# power_supply.net
KiCad netlist of a schematic drawn in Altium Designer
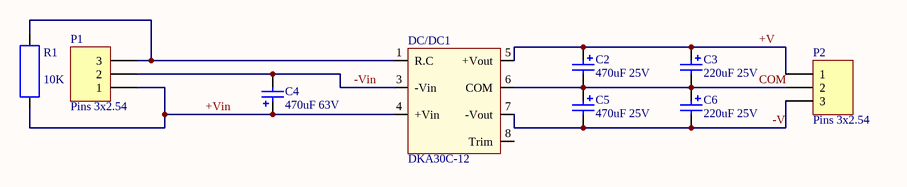
[diagram p0: power_supply.SchDoc]

(export (version "E")
  (design (tool "Eeschema 10.0.6"))
  (components
    (comp (ref "C2")
      (value "470uF 25V")
      (footprint "Cond 10mm 25V")
      (libsource (lib "A_H_sch_lib") (part "Cond_polar"))
    )
    (comp (ref "C3")
      (value "220uF 25V")
      (footprint "A_H_pcb_lib:Cond 8mm 25V")
      (libsource (lib "A_H_sch_lib") (part "Cond_polar"))
    )
    (comp (ref "C4")
      (value "470uF 63V")
      (footprint "A_H_pcb_lib:Cond 12mm 63V")
      (libsource (lib "A_H_sch_lib") (part "Cond_polar"))
    )
    (comp (ref "C5")
      (value "470uF 25V")
      (footprint "Cond 10mm 25V")
      (libsource (lib "A_H_sch_lib") (part "Cond_polar"))
    )
    (comp (ref "C6")
      (value "220uF 25V")
      (footprint "A_H_pcb_lib:Cond 8mm 25V")
      (libsource (lib "A_H_sch_lib") (part "Cond_polar"))
    )
    (comp (ref "DC/DC1")
      (value "DKA30C-12")
      (footprint "A_H_pcb_lib:MW_DKA30C-12")
      (libsource (lib "A_H_sch_lib") (part "MW_DKA30C-12"))
    )
    (comp (ref "P1")
      (value "Pins 3x2.54")
      (footprint "Pins 3x2.54")
      (libsource (lib "A_H_sch_lib") (part "Pins 3x2.54"))
    )
    (comp (ref "P2")
      (value "Pins 3x2.54")
      (footprint "Pins 3x2.54")
      (libsource (lib "") (part "Pins 3x2.54_1"))
    )
    (comp (ref "R1") (value "10K") (footprint "R0805") (libsource (lib "A_H_sch_lib") (part "Resistor")))
  )
  (nets
    (net (code "1") (name "/+V") (class "Default")
      (node (ref "C2") (pin "1") (pinfunction "1_1") (pintype "passive"))
      (node (ref "C3") (pin "1") (pinfunction "1_1") (pintype "passive"))
      (node (ref "DC/DC1") (pin "5") (pinfunction "+Vout_5") (pintype "passive"))
      (node (ref "P2") (pin "1") (pinfunction "1_1") (pintype "passive"))
    )
    (net (code "2") (name "/+Vin") (class "Default")
      (node (ref "C4") (pin "1") (pinfunction "1_1") (pintype "passive"))
      (node (ref "DC/DC1") (pin "4") (pinfunction "+Vin_4") (pintype "passive"))
      (node (ref "P1") (pin "1") (pinfunction "1_1") (pintype "passive"))
      (node (ref "R1") (pin "1") (pinfunction "1_1") (pintype "passive"))
    )
    (net (code "3") (name "/-V") (class "Default")
      (node (ref "C5") (pin "2") (pinfunction "2_2") (pintype "passive"))
      (node (ref "C6") (pin "2") (pinfunction "2_2") (pintype "passive"))
      (node (ref "DC/DC1") (pin "7") (pinfunction "-Vout_7") (pintype "passive"))
      (node (ref "P2") (pin "3") (pinfunction "3_3") (pintype "passive"))
    )
    (net (code "4") (name "/-Vin") (class "Default")
      (node (ref "C4") (pin "2") (pinfunction "2_2") (pintype "passive"))
      (node (ref "DC/DC1") (pin "3") (pinfunction "-Vin_3") (pintype "passive"))
      (node (ref "P1") (pin "2") (pinfunction "2_2") (pintype "passive"))
    )
    (net (code "5") (name "/COM") (class "Default")
      (node (ref "C2") (pin "2") (pinfunction "2_2") (pintype "passive"))
      (node (ref "C3") (pin "2") (pinfunction "2_2") (pintype "passive"))
      (node (ref "C5") (pin "1") (pinfunction "1_1") (pintype "passive"))
      (node (ref "C6") (pin "1") (pinfunction "1_1") (pintype "passive"))
      (node (ref "DC/DC1") (pin "6") (pinfunction "COM_6") (pintype "passive"))
      (node (ref "P2") (pin "2") (pinfunction "2_2") (pintype "passive"))
    )
    (net (code "6") (name "Net-(DC/DC1-R.C)") (class "Default")
      (node (ref "DC/DC1") (pin "1") (pinfunction "R.C_1") (pintype "passive"))
      (node (ref "P1") (pin "3") (pinfunction "3_3") (pintype "passive"))
      (node (ref "R1") (pin "2") (pinfunction "2_2") (pintype "passive"))
    )
    (net (code "7") (name "unconnected-(DC/DC1-Trim-Pad8)") (class "Default")
      (node (ref "DC/DC1") (pin "8") (pinfunction "Trim_8") (pintype "passive"))
    )
  )
)
